# Ethernet_CTRL.net
KiCad netlist of a schematic drawn in Altium Designer
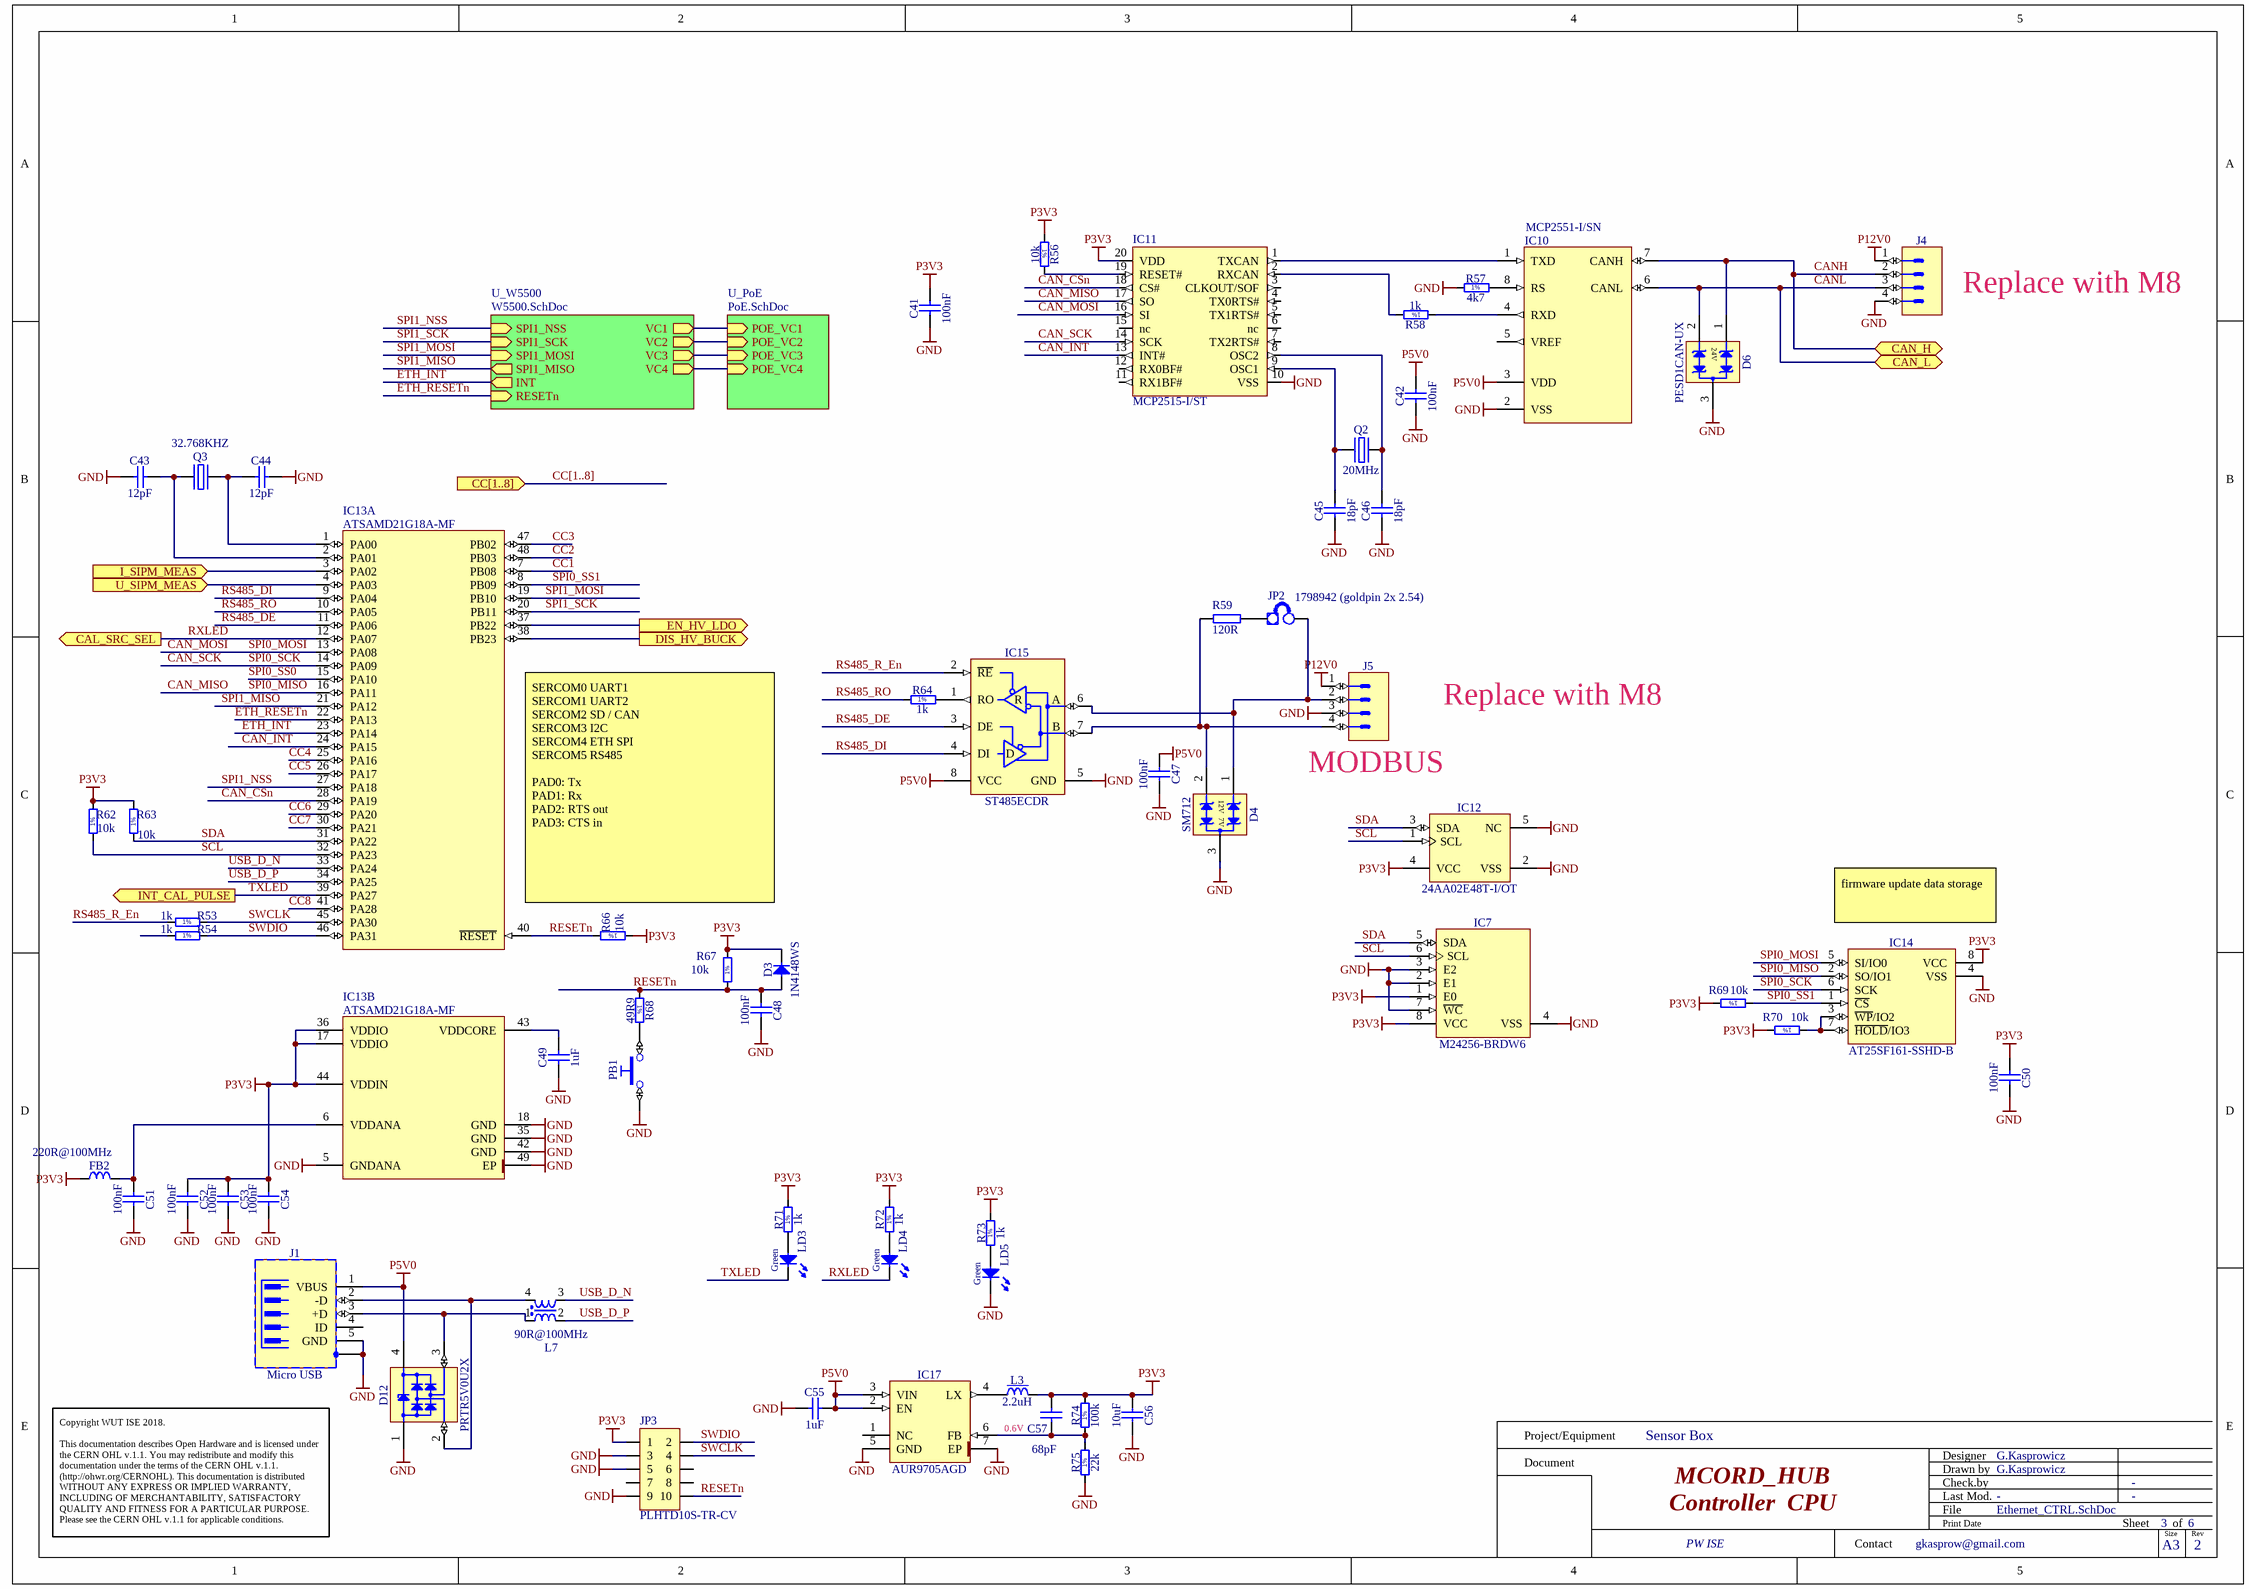
[diagram p0: Ethernet_CTRL.SchDoc]

(export (version "E")
  (design (tool "Eeschema 10.0.6"))
  (components
    (comp (ref "C41")
      (value "100nF")
      (footprint "CAPC1005X55N")
      (description "Non-polarised capacitor")
      (fields
        (field (name "PART NUMBER") "CC0402_100NF_16V_10%_X5R")
        (field (name "VOLTAGE") "16V")
        (field (name "AUTHOR") "CERN DEM JLC")
      )
      (libsource (lib "Capacitors") (part "Capacitor - non polarized"))
    )
    (comp (ref "C42")
      (value "100nF")
      (footprint "CAPC1005X55N")
      (description "Non-polarised capacitor")
      (fields
        (field (name "PART NUMBER") "CC0402_100NF_16V_10%_X5R")
        (field (name "VOLTAGE") "16V")
        (field (name "AUTHOR") "CERN DEM JLC")
      )
      (libsource (lib "Capacitors") (part "Capacitor - non polarized"))
    )
    (comp (ref "C43")
      (value "12pF")
      (footprint "CAPC1005X55N")
      (description "Non-polarised capacitor")
      (fields
        (field (name "PART NUMBER") "CC0402_12PF_50V_5%_C0G")
        (field (name "VOLTAGE") "50V")
        (field (name "AUTHOR") "CERN DEM JLC")
      )
      (libsource (lib "Capacitors") (part "Capacitor - non polarized"))
    )
    (comp (ref "C44")
      (value "12pF")
      (footprint "CAPC1005X55N")
      (description "Non-polarised capacitor")
      (fields
        (field (name "PART NUMBER") "CC0402_12PF_50V_5%_C0G")
        (field (name "VOLTAGE") "50V")
        (field (name "AUTHOR") "CERN DEM JLC")
      )
      (libsource (lib "Capacitors") (part "Capacitor - non polarized"))
    )
    (comp (ref "C45")
      (value "18pF")
      (footprint "CAPC1005X55N")
      (description "Non-polarised capacitor")
      (fields
        (field (name "PART NUMBER") "CC0402_18PF_50V_5%_C0G")
        (field (name "VOLTAGE") "50V")
        (field (name "AUTHOR") "CERN DEM JLC")
      )
      (libsource (lib "Capacitors") (part "Capacitor - non polarized"))
    )
    (comp (ref "C46")
      (value "18pF")
      (footprint "CAPC1005X55N")
      (description "Non-polarised capacitor")
      (fields
        (field (name "PART NUMBER") "CC0402_18PF_50V_5%_C0G")
        (field (name "VOLTAGE") "50V")
        (field (name "AUTHOR") "CERN DEM JLC")
      )
      (libsource (lib "Capacitors") (part "Capacitor - non polarized"))
    )
    (comp (ref "C47")
      (value "100nF")
      (footprint "CAPC1005X55N")
      (description "Non-polarised capacitor")
      (fields
        (field (name "PART NUMBER") "CC0402_100NF_16V_10%_X7R")
        (field (name "VOLTAGE") "16V")
        (field (name "AUTHOR") "CERN DEM JLC")
      )
      (libsource (lib "Capacitors") (part "Capacitor - non polarized"))
    )
    (comp (ref "C48")
      (value "100nF")
      (footprint "CAPC1005X55N")
      (description "Non-polarised capacitor")
      (fields
        (field (name "PART NUMBER") "CC0402_100NF_16V_10%_X7R")
        (field (name "VOLTAGE") "16V")
        (field (name "AUTHOR") "CERN DEM JLC")
      )
      (libsource (lib "Capacitors") (part "Capacitor - non polarized"))
    )
    (comp (ref "C49")
      (value "1uF")
      (footprint "CAPC1608X87N")
      (description "Non-polarised capacitor")
      (fields
        (field (name "PART NUMBER") "CC0603_1UF_16V_10%_X7R")
        (field (name "VOLTAGE") "16V")
        (field (name "AUTHOR") "CERN DEM JLC")
      )
      (libsource (lib "Capacitors") (part "Capacitor - non polarized"))
    )
    (comp (ref "C50")
      (value "100nF")
      (footprint "CAPC1005X55N")
      (description "Non-polarised capacitor")
      (fields
        (field (name "PART NUMBER") "CC0402_100NF_16V_10%_X7R")
        (field (name "VOLTAGE") "16V")
        (field (name "AUTHOR") "CERN DEM JLC")
      )
      (libsource (lib "Capacitors") (part "Capacitor - non polarized"))
    )
    (comp (ref "C51")
      (value "100nF")
      (footprint "CAPC1005X55N")
      (description "Non-polarised capacitor")
      (fields
        (field (name "PART NUMBER") "CC0402_100NF_16V_10%_X7R")
        (field (name "VOLTAGE") "16V")
        (field (name "AUTHOR") "CERN DEM JLC")
      )
      (libsource (lib "Capacitors") (part "Capacitor - non polarized"))
    )
    (comp (ref "C52")
      (value "100nF")
      (footprint "CAPC1005X55N")
      (description "Non-polarised capacitor")
      (fields
        (field (name "PART NUMBER") "CC0402_100NF_16V_10%_X7R")
        (field (name "VOLTAGE") "16V")
        (field (name "AUTHOR") "CERN DEM JLC")
      )
      (libsource (lib "Capacitors") (part "Capacitor - non polarized"))
    )
    (comp (ref "C53")
      (value "100nF")
      (footprint "CAPC1005X55N")
      (description "Non-polarised capacitor")
      (fields
        (field (name "PART NUMBER") "CC0402_100NF_16V_10%_X7R")
        (field (name "VOLTAGE") "16V")
        (field (name "AUTHOR") "CERN DEM JLC")
      )
      (libsource (lib "Capacitors") (part "Capacitor - non polarized"))
    )
    (comp (ref "C54")
      (value "100nF")
      (footprint "CAPC1005X55N")
      (description "Non-polarised capacitor")
      (fields
        (field (name "PART NUMBER") "CC0402_100NF_16V_10%_X7R")
        (field (name "VOLTAGE") "16V")
        (field (name "AUTHOR") "CERN DEM JLC")
      )
      (libsource (lib "Capacitors") (part "Capacitor - non polarized"))
    )
    (comp (ref "C55")
      (value "1uF")
      (footprint "CAPC1005X55N")
      (description "Non-polarised capacitor")
      (fields
        (field (name "PART NUMBER") "CC0402_1UF_16V_10%_X5R")
        (field (name "VOLTAGE") "16V")
        (field (name "AUTHOR") "CERN DEM JLC")
      )
      (libsource (lib "Capacitors") (part "Capacitor - non polarized"))
    )
    (comp (ref "C56")
      (value "10uF")
      (footprint "CAPC2012X135N")
      (description "Non-polarised capacitor")
      (fields
        (field (name "PART NUMBER") "CC0805_10UF_16V_10%_X5R")
        (field (name "VOLTAGE") "16V")
        (field (name "AUTHOR") "CERN DEM JLC")
      )
      (libsource (lib "Capacitors") (part "Capacitor - non polarized"))
    )
    (comp (ref "C57")
      (value "68pF")
      (footprint "CAPC1608X87N")
      (description "Non-polarised capacitor")
      (fields
        (field (name "PART NUMBER") "CC0603_68PF_50V_5%_NP0")
        (field (name "VOLTAGE") "50V")
        (field (name "AUTHOR") "CERN DEM JLC")
      )
      (libsource (lib "Capacitors") (part "Capacitor - non polarized"))
    )
    (comp (ref "D3")
      (value "1N4148WS")
      (footprint "SODFL2512X100N")
      (description "Diode")
      (fields
        (field (name "VOLTAGE") "75V")
        (field (name "POWER") "150mA")
        (field (name "AUTHOR") "CERN DEM JLC")
      )
      (libsource (lib "ICs And Semiconductors") (part "Diode"))
    )
    (comp (ref "D4")
      (value "SM712")
      (footprint "SOT95P237X112-3N")
      (description "Asymmetrical TVS Diode for Extended Common-Mode RS-485")
      (fields
        (field (name "VOLTAGE") "12V/-7V")
        (field (name "POWER") "400W")
        (field (name "AUTHOR") "CERN DEM JLC")
      )
      (libsource (lib "ICs And Semiconductors") (part "SM712"))
    )
    (comp (ref "D6")
      (value "PESD1CAN-UX")
      (footprint "SOT95P237X112-3N")
      (description "TVS Diode for CAN")
      (fields
        (field (name "VOLTAGE") "24V")
        (field (name "POWER") "400W")
        (field (name "AUTHOR") "CERN DEM JLC")
      )
      (libsource (lib "LIBRARY_SCH") (part "D_TVS_PESD1CAN"))
    )
    (comp (ref "D12")
      (value "PRTR5V0U2X")
      (footprint "SOT190P230X110-4N")
      (description "Ultra Low Capacitance Double Rail-to-Rail ESD Protection Diode")
      (fields
        (field (name "VOLTAGE") "5.5V")
        (field (name "MANUFACTURER") "NXP SEMICONDUCTORS")
        (field (name "AUTHOR") "CERN DEM JLC")
      )
      (libsource (lib "ICs And Semiconductors") (part "PRTR5V0U2X"))
    )
    (comp (ref "FB2")
      (value "220R@100MHz")
      (footprint "INDC2012X105N")
      (description "Inductor")
      (fields
        (field (name "PART NUMBER") "IND0805_MURATA_BLM21PG221SN1D")
        (field (name "POWER") "2A")
        (field (name "AUTHOR") "CERN DEM JLC")
      )
      (libsource (lib "Inductors & Transformers") (part "Inductor"))
    )
    (comp (ref "IC7")
      (value "M24256-BRDW6")
      (footprint "SOP65P640X120-8N")
      (description "256-Kbit Serial I²C Bus EEPROM")
      (fields
        (field (name "PART NUMBER") "M24256-BRDW6P")
        (field (name "MANUFACTURER") "ST MICROELECTRONICS")
        (field (name "AUTHOR") "CERN DEM MR")
      )
      (libsource (lib "LIBRARY_SCH") (part "MEM_M24256-BRDW6P"))
    )
    (comp (ref "IC10")
      (value "MCP2551-I/SN")
      (footprint "SOIC127P600X175-8N")
      (description "High-Speed CAN Transceiver, 8-Pin SOIC, Industrial Temperature")
      (fields (field (name "MANUFACTURER") "MICROCHIP TECHNOLOGY") (field (name "AUTHOR") "GK"))
      (libsource (lib "LIBRARY_SCH") (part "IFC_MCP2551"))
    )
    (comp (ref "IC11")
      (value "MCP2515-I/ST")
      (footprint "SOP65P640X110-20N")
      (description "CAN Controller With SPI nterface")
      (fields
        (field (name "MANUFACTURER") "Microchip")
        (field (name "MANUFACTURER PART NUMBER") "MCP2515T-I/ST")
      )
      (libsource (lib "LIBRARY_SCH") (part "IFC_MCP2515_TSSOP"))
    )
    (comp (ref "IC12")
      (value "24AA02E48T-I/OT")
      (footprint "SOT95P280X145-5N")
      (description "1.7V-5.5V, 2K I2C Serial EEPROM With EUI-48 Node Identity")
      (fields (field (name "MANUFACTURER") "MICROCHIP TECHNOLOGY") (field (name "AUTHOR") "CERN DEM MR"))
      (libsource (lib "ICs And Semiconductors") (part "24AA02E48T-I/OT"))
    )
    (comp (ref "IC13")
      (value "ATSAMD21G18A-MF")
      (footprint "QFN50P700X700X100-49N-S525")
      (fields (field (name "MANUFACTURER") "MICROCHIP") (field (name "AUTHOR") "CERN DEM BC"))
      (libsource (lib "ICs And Semiconductors") (part "ATSAMD21G18A-MF"))
    )
    (comp (ref "IC14")
      (value "AT25SF161-SSHD-B")
      (footprint "SOIC127P790X216-8N")
      (description "16Mb, 3V, Multiple I/O Serial NOR Flash Memory")
      (fields (field (name "AUTHOR") "GK"))
      (libsource (lib "LIBRARY_SCH") (part "MEM_AT25SF161"))
    )
    (comp (ref "IC15")
      (value "ST485ECDR")
      (footprint "SOIC127P600X175-8N")
      (description "±15kV ESD-Protected, Low Power  RS-485/RS-422 Transceiver")
      (fields (field (name "MANUFACTURER") "ST MICROELECTRONICS") (field (name "AUTHOR") "CERN DEM MR"))
      (libsource (lib "ICs And Semiconductors") (part "ST485EC"))
    )
    (comp (ref "IC17")
      (value "AUR9705AGD")
      (footprint "SON65P200X200X80-7N-R65X145")
      (description "0V to 6V Input, 1A, 1.5MHz, Step-Down DC-DC Converter")
      (fields (field (name "MANUFACTURER") "DIODES INCORPORATED") (field (name "AUTHOR") "CERN DEM MR"))
      (libsource (lib "ICs And Semiconductors") (part "AUR9705AGD"))
    )
    (comp (ref "J1")
      (value "Micro USB")
      (footprint "FCI_10118194-0001LF")
      (description "5 Pin + 1 Shield USB Receptacle")
      (fields
        (field (name "PART NUMBER") "FCI_10118194-0001LF")
        (field (name "MANUFACTURER") "FCI")
        (field (name "AUTHOR") "CERN DEM JLC")
      )
      (libsource (lib "Connectors") (part "Connector USB 5 Pin + 1Shield"))
    )
    (comp (ref "J4")
      (value "~")
      (footprint "FCI_20020110-D041A01LF")
      (description "Connector 4 Male")
      (fields
        (field (name "PART NUMBER") "FCI_20020110-D041A01LF")
        (field (name "MANUFACTURER") "FCI")
        (field (name "AUTHOR") "CERN DEM JLC")
      )
      (libsource (lib "Connectors") (part "Connector 4 Male"))
    )
    (comp (ref "J5")
      (value "~")
      (footprint "FCI_20020110-D041A01LF")
      (description "Connector 4 Male")
      (fields
        (field (name "PART NUMBER") "FCI_20020110-D041A01LF")
        (field (name "MANUFACTURER") "FCI")
        (field (name "AUTHOR") "CERN DEM JLC")
      )
      (libsource (lib "Connectors") (part "Connector 4 Male"))
    )
    (comp (ref "JP2")
      (value "1798942 (goldpin 2x 2.54)")
      (footprint "jump")
      (description "Jumper")
      (libsource (lib "LIBRARY_SCH") (part "JUMPER"))
    )
    (comp (ref "JP3")
      (value "PLHTD10S-TR-CV")
      (footprint "PLHTD10S-TR-CV")
      (description "1.27 mm dual row goldpin (Maritex)")
      (libsource (lib "LIBRARY_SCH") (part "CON_2x5 1.27 SMT Male"))
    )
    (comp (ref "L3")
      (value "2.2uH")
      (footprint "IND_MURATA_LQH44PN_P0")
      (description "Inductor With Core")
      (fields
        (field (name "PART NUMBER") "IND_2.2UH_20%_MURATA_LQH44PN2R2MP0L")
        (field (name "POWER") "1.8A")
        (field (name "AUTHOR") "CERN DEM JLC")
      )
      (libsource (lib "Inductors & Transformers") (part "Inductor With Magnetic core"))
    )
    (comp (ref "L7")
      (value "90R@100MHz")
      (footprint "IND_MURATA_DLW21S")
      (description "Inductor Common Mode")
      (fields
        (field (name "PART NUMBER") "IND_MURATA_DLW21SN900SQ2L")
        (field (name "POWER") "330mA")
        (field (name "AUTHOR") "CERN DEM JLC")
      )
      (libsource (lib "Inductors & Transformers") (part "Inductor Common Mode 1Dot-2 4Dot-3"))
    )
    (comp (ref "LD3")
      (value "Green")
      (footprint "LED_AVAGO_HSME-C120")
      (description "LED Green 1C 2A")
      (fields
        (field (name "PART NUMBER") "LED_AVAGO_HSME-C120")
        (field (name "MANUFACTURER") "AVAGO TECHNOLOGIES")
        (field (name "AUTHOR") "CERN DEM JMW")
      )
      (libsource (lib "ICs And Semiconductors") (part "LED Green 1C 2A"))
    )
    (comp (ref "LD4")
      (value "Green")
      (footprint "LED_AVAGO_HSME-C120")
      (description "LED Green 1C 2A")
      (fields
        (field (name "PART NUMBER") "LED_AVAGO_HSME-C120")
        (field (name "MANUFACTURER") "AVAGO TECHNOLOGIES")
        (field (name "AUTHOR") "CERN DEM JMW")
      )
      (libsource (lib "ICs And Semiconductors") (part "LED Green 1C 2A"))
    )
    (comp (ref "LD5")
      (value "Green")
      (footprint "LED_AVAGO_HSME-C120")
      (description "LED Green 1C 2A")
      (fields
        (field (name "PART NUMBER") "LED_AVAGO_HSME-C120")
        (field (name "MANUFACTURER") "AVAGO TECHNOLOGIES")
        (field (name "AUTHOR") "CERN DEM JMW")
      )
      (libsource (lib "ICs And Semiconductors") (part "LED Green 1C 2A"))
    )
    (comp (ref "PB1")
      (value "Push Button")
      (footprint "PB_TYCO_FSMSM")
      (description "Push-Button Switch SPDT")
      (fields
        (field (name "PART NUMBER") "PB_TYCO_FSMSM")
        (field (name "MANUFACTURER") "TYCO ELECTRONICS")
        (field (name "AUTHOR") "CERN DEM JLC")
      )
      (libsource (lib "Eletro-mechanical") (part "PB SPST 1NO-2NO"))
    )
    (comp (ref "Q2")
      (value "20MHz")
      (footprint "XTAL1160X490X430")
      (description "Quartz Crystal 20MHz, 30ppm, 20pF")
      (fields
        (field (name "PART NUMBER") "SR PASSIVES 20M-49SMD-SR")
        (field (name "MANUFACTURER") "SR PASSIVES")
        (field (name "AUTHOR") "GK")
      )
      (libsource (lib "LIBRARY_SCH") (part "X_CRYSTAL_20M_HC49"))
    )
    (comp (ref "Q3")
      (value "32.768KHZ")
      (footprint "XTAL_ABRACON_ABS09")
      (description "Quartz Crystal")
      (fields
        (field (name "PART NUMBER") "XTAL_32.768KHZ_ABRACON_ABS09-32.768KHZ-T")
        (field (name "MANUFACTURER") "ABRACON")
        (field (name "AUTHOR") "CERN DEM JLC")
      )
      (libsource (lib "ICs And Semiconductors") (part "Quartz Crystal"))
    )
    (comp (ref "R53")
      (value "1k")
      (footprint "RESC1005X40N")
      (description "Resistor - 1%")
      (fields
        (field (name "PART NUMBER") "R0402_1K_1%_0.0625W_100PPM")
        (field (name "POWER") "0.0625W")
        (field (name "AUTHOR") "CERN DEM JLC")
      )
      (libsource (lib "Resistors") (part "Resistor - 1%"))
    )
    (comp (ref "R54")
      (value "1k")
      (footprint "RESC1005X40N")
      (description "Resistor - 1%")
      (fields
        (field (name "PART NUMBER") "R0402_1K_1%_0.0625W_100PPM")
        (field (name "POWER") "0.0625W")
        (field (name "AUTHOR") "CERN DEM JLC")
      )
      (libsource (lib "Resistors") (part "Resistor - 1%"))
    )
    (comp (ref "R56")
      (value "10k")
      (footprint "RESC1005X40N")
      (description "Resistor - 1%")
      (fields
        (field (name "PART NUMBER") "R0402_10K_1%_0.0625W_100PPM")
        (field (name "POWER") "0.0625W")
        (field (name "AUTHOR") "CERN DEM JLC")
      )
      (libsource (lib "Resistors") (part "Resistor - 1%"))
    )
    (comp (ref "R57")
      (value "4k7")
      (footprint "RESC1005X40N")
      (description "Resistor - 1%")
      (fields
        (field (name "PART NUMBER") "R0402_4K7_1%_0.0625W_100PPM")
        (field (name "POWER") "0.0625W")
        (field (name "AUTHOR") "CERN DEM JLC")
      )
      (libsource (lib "Resistors") (part "Resistor - 1%"))
    )
    (comp (ref "R58")
      (value "1k")
      (footprint "RESC1005X40N")
      (description "Resistor - 1%")
      (fields
        (field (name "PART NUMBER") "R0402_1K_1%_0.0625W_100PPM")
        (field (name "POWER") "0.0625W")
        (field (name "AUTHOR") "CERN DEM JLC")
      )
      (libsource (lib "Resistors") (part "Resistor - 1%"))
    )
    (comp (ref "R59")
      (value "120R")
      (footprint "1206R")
      (description "SMD Resistor")
      (libsource (lib "LIBRARY_SCH") (part "RES_1206"))
    )
    (comp (ref "R62")
      (value "10k")
      (footprint "RESC1005X40N")
      (description "Resistor - 1%")
      (fields
        (field (name "PART NUMBER") "R0402_10K_1%_0.0625W_100PPM")
        (field (name "POWER") "0.0625W")
        (field (name "AUTHOR") "CERN DEM JLC")
      )
      (libsource (lib "Resistors") (part "Resistor - 1%"))
    )
    (comp (ref "R63")
      (value "10k")
      (footprint "RESC1005X40N")
      (description "Resistor - 1%")
      (fields
        (field (name "PART NUMBER") "R0402_10K_1%_0.0625W_100PPM")
        (field (name "POWER") "0.0625W")
        (field (name "AUTHOR") "CERN DEM JLC")
      )
      (libsource (lib "Resistors") (part "Resistor - 1%"))
    )
    (comp (ref "R64")
      (value "1k")
      (footprint "RESC1005X40N")
      (description "Resistor - 1%")
      (fields
        (field (name "PART NUMBER") "R0402_1K_1%_0.0625W_100PPM")
        (field (name "POWER") "0.0625W")
        (field (name "AUTHOR") "CERN DEM JLC")
      )
      (libsource (lib "Resistors") (part "Resistor - 1%"))
    )
    (comp (ref "R66")
      (value "10k")
      (footprint "RESC1005X40N")
      (description "Resistor - 1%")
      (fields
        (field (name "PART NUMBER") "R0402_10K_1%_0.0625W_100PPM")
        (field (name "POWER") "0.0625W")
        (field (name "AUTHOR") "CERN DEM JLC")
      )
      (libsource (lib "Resistors") (part "Resistor - 1%"))
    )
    (comp (ref "R67")
      (value "10k")
      (footprint "RESC1005X40N")
      (description "Resistor - 1%")
      (fields
        (field (name "PART NUMBER") "R0402_10K_1%_0.0625W_100PPM")
        (field (name "POWER") "0.0625W")
        (field (name "AUTHOR") "CERN DEM JLC")
      )
      (libsource (lib "Resistors") (part "Resistor - 1%"))
    )
    (comp (ref "R68")
      (value "49R9")
      (footprint "RESC1005X40N")
      (description "Resistor - 1%")
      (fields
        (field (name "PART NUMBER") "R0402_49R9_1%_0.0625W_100PPM")
        (field (name "POWER") "0.0625W")
        (field (name "AUTHOR") "CERN DEM JLC")
      )
      (libsource (lib "Resistors") (part "Resistor - 1%"))
    )
    (comp (ref "R69")
      (value "10k")
      (footprint "RESC1005X40N")
      (description "Resistor - 1%")
      (fields
        (field (name "PART NUMBER") "R0402_10K_1%_0.0625W_100PPM")
        (field (name "POWER") "0.0625W")
        (field (name "AUTHOR") "CERN DEM JLC")
      )
      (libsource (lib "Resistors") (part "Resistor - 1%"))
    )
    (comp (ref "R70")
      (value "10k")
      (footprint "RESC1005X40N")
      (description "Resistor - 1%")
      (fields
        (field (name "PART NUMBER") "R0402_10K_1%_0.0625W_100PPM")
        (field (name "POWER") "0.0625W")
        (field (name "AUTHOR") "CERN DEM JLC")
      )
      (libsource (lib "Resistors") (part "Resistor - 1%"))
    )
    (comp (ref "R71")
      (value "1k")
      (footprint "RESC1005X40N")
      (description "Resistor - 1%")
      (fields
        (field (name "PART NUMBER") "R0402_1K_1%_0.0625W_100PPM")
        (field (name "POWER") "0.0625W")
        (field (name "AUTHOR") "CERN DEM JLC")
      )
      (libsource (lib "Resistors") (part "Resistor - 1%"))
    )
    (comp (ref "R72")
      (value "1k")
      (footprint "RESC1005X40N")
      (description "Resistor - 1%")
      (fields
        (field (name "PART NUMBER") "R0402_1K_1%_0.0625W_100PPM")
        (field (name "POWER") "0.0625W")
        (field (name "AUTHOR") "CERN DEM JLC")
      )
      (libsource (lib "Resistors") (part "Resistor - 1%"))
    )
    (comp (ref "R73")
      (value "1k")
      (footprint "RESC1005X40N")
      (description "Resistor - 1%")
      (fields
        (field (name "PART NUMBER") "R0402_1K_1%_0.0625W_100PPM")
        (field (name "POWER") "0.0625W")
        (field (name "AUTHOR") "CERN DEM JLC")
      )
      (libsource (lib "Resistors") (part "Resistor - 1%"))
    )
    (comp (ref "R74")
      (value "100k")
      (footprint "RESC1005X40N")
      (description "Resistor - 1%")
      (fields
        (field (name "PART NUMBER") "R0402_100K_1%_0.0625W_100PPM")
        (field (name "POWER") "0.0625W")
        (field (name "AUTHOR") "CERN DEM JLC")
      )
      (libsource (lib "Resistors") (part "Resistor - 1%"))
    )
    (comp (ref "R75")
      (value "22k")
      (footprint "RESC1005X40N")
      (description "Resistor - 1%")
      (fields
        (field (name "PART NUMBER") "R0402_22K_1%_0.0625W_100PPM")
        (field (name "POWER") "0.0625W")
        (field (name "AUTHOR") "CERN DEM JLC")
      )
      (libsource (lib "Resistors") (part "Resistor - 1%"))
    )
  )
  (nets
    (net (code "1") (name "/CANH") (class "Default")
      (node (ref "D6") (pin "1") (pinfunction "I/O1_1") (pintype "passive"))
      (node (ref "IC10") (pin "7") (pinfunction "CANH_7") (pintype "bidirectional"))
      (node (ref "J4") (pin "2") (pinfunction "2_2") (pintype "bidirectional"))
    )
    (net (code "2") (name "/CANL") (class "Default")
      (node (ref "D6") (pin "2") (pinfunction "I/O2_2") (pintype "passive"))
      (node (ref "IC10") (pin "6") (pinfunction "CANL_6") (pintype "bidirectional"))
      (node (ref "J4") (pin "3") (pinfunction "3_3") (pintype "bidirectional"))
    )
    (net (code "3") (name "/CAN_CSn") (class "Default")
      (node (ref "IC11") (pin "18") (pinfunction "CS#_18") (pintype "output"))
      (node (ref "IC13") (pin "28") (pinfunction "PA19_28") (pintype "bidirectional"))
    )
    (net (code "4") (name "/CAN_INT") (class "Default")
      (node (ref "IC11") (pin "13") (pinfunction "INT#_13") (pintype "output"))
      (node (ref "IC13") (pin "24") (pinfunction "PA15_24") (pintype "bidirectional"))
    )
    (net (code "5") (name "/CAN_MISO") (class "Default")
      (node (ref "IC11") (pin "17") (pinfunction "SO_17") (pintype "output"))
      (node (ref "IC13") (pin "16") (pinfunction "PA11_16") (pintype "bidirectional"))
      (node (ref "IC14") (pin "2") (pinfunction "SO/IO1_2") (pintype "bidirectional"))
    )
    (net (code "6") (name "/CAN_MOSI") (class "Default")
      (node (ref "IC11") (pin "16") (pinfunction "SI_16") (pintype "input"))
      (node (ref "IC13") (pin "13") (pinfunction "PA08_13") (pintype "bidirectional"))
      (node (ref "IC14") (pin "5") (pinfunction "SI/IO0_5") (pintype "bidirectional"))
    )
    (net (code "7") (name "/CAN_SCK") (class "Default")
      (node (ref "IC11") (pin "14") (pinfunction "SCK_14") (pintype "input"))
      (node (ref "IC13") (pin "14") (pinfunction "PA09_14") (pintype "bidirectional"))
      (node (ref "IC14") (pin "6") (pinfunction "SCK_6") (pintype "input"))
    )
    (net (code "8") (name "/CC1") (class "Default")
      (node (ref "IC13") (pin "7") (pinfunction "PB08_7") (pintype "bidirectional"))
    )
    (net (code "9") (name "/CC2") (class "Default")
      (node (ref "IC13") (pin "48") (pinfunction "PB03_48") (pintype "bidirectional"))
    )
    (net (code "10") (name "/CC3") (class "Default")
      (node (ref "IC13") (pin "47") (pinfunction "PB02_47") (pintype "bidirectional"))
    )
    (net (code "11") (name "/CC4") (class "Default")
      (node (ref "IC13") (pin "25") (pinfunction "PA16_25") (pintype "bidirectional"))
    )
    (net (code "12") (name "/CC5") (class "Default")
      (node (ref "IC13") (pin "26") (pinfunction "PA17_26") (pintype "bidirectional"))
    )
    (net (code "13") (name "/CC6") (class "Default")
      (node (ref "IC13") (pin "29") (pinfunction "PA20_29") (pintype "bidirectional"))
    )
    (net (code "14") (name "/CC7") (class "Default")
      (node (ref "IC13") (pin "30") (pinfunction "PA21_30") (pintype "bidirectional"))
    )
    (net (code "15") (name "/CC8") (class "Default")
      (node (ref "IC13") (pin "41") (pinfunction "PA28_41") (pintype "bidirectional"))
    )
    (net (code "17") (name "/DIS_HV_BUCK") (class "Default")
      (node (ref "IC13") (pin "38") (pinfunction "PB23_38") (pintype "bidirectional"))
    )
    (net (code "18") (name "/EN_HV_LDO") (class "Default")
      (node (ref "IC13") (pin "37") (pinfunction "PB22_37") (pintype "bidirectional"))
    )
    (net (code "19") (name "/ETH_INT") (class "Default")
      (node (ref "IC13") (pin "23") (pinfunction "PA14_23") (pintype "bidirectional"))
    )
    (net (code "20") (name "/ETH_RESETn") (class "Default")
      (node (ref "IC13") (pin "22") (pinfunction "PA13_22") (pintype "bidirectional"))
    )
    (net (code "21") (name "/I_SIPM_MEAS") (class "Default")
      (node (ref "IC13") (pin "3") (pinfunction "PA02_3") (pintype "bidirectional"))
    )
    (net (code "22") (name "/RESETn") (class "Default")
      (node (ref "C48") (pin "1") (pinfunction "1_1") (pintype "passive"))
      (node (ref "D3") (pin "2") (pinfunction "A_2") (pintype "passive"))
      (node (ref "IC13") (pin "40") (pinfunction "~{RESET}_40") (pintype "input"))
      (node (ref "JP3") (pin "10") (pinfunction "10_10") (pintype "passive"))
      (node (ref "R66") (pin "2") (pinfunction "2_2") (pintype "passive"))
      (node (ref "R67") (pin "1") (pinfunction "1_1") (pintype "passive"))
      (node (ref "R68") (pin "1") (pinfunction "1_1") (pintype "passive"))
    )
    (net (code "23") (name "/RS485_DE") (class "Default")
      (node (ref "IC13") (pin "11") (pinfunction "PA06_11") (pintype "bidirectional"))
      (node (ref "IC15") (pin "3") (pinfunction "DE_3") (pintype "input"))
    )
    (net (code "24") (name "/RS485_DI") (class "Default")
      (node (ref "IC13") (pin "9") (pinfunction "PA04_9") (pintype "bidirectional"))
      (node (ref "IC15") (pin "4") (pinfunction "DI_4") (pintype "input"))
    )
    (net (code "25") (name "/RS485_RO") (class "Default")
      (node (ref "IC13") (pin "10") (pinfunction "PA05_10") (pintype "bidirectional"))
      (node (ref "R64") (pin "1") (pinfunction "1_1") (pintype "passive"))
    )
    (net (code "26") (name "/RS485_R_En") (class "Default")
      (node (ref "IC15") (pin "2") (pinfunction "~{RE}_2") (pintype "input"))
      (node (ref "R53") (pin "1") (pinfunction "1_1") (pintype "passive"))
    )
    (net (code "27") (name "/RXLED") (class "Default")
      (node (ref "IC13") (pin "12") (pinfunction "PA07_12") (pintype "bidirectional"))
      (node (ref "LD4") (pin "1") (pinfunction "C_1") (pintype "passive"))
    )
    (net (code "28") (name "/SCL") (class "Default")
      (node (ref "IC12") (pin "1") (pinfunction "SCL_1") (pintype "input"))
      (node (ref "IC13") (pin "32") (pinfunction "PA23_32") (pintype "bidirectional"))
      (node (ref "IC7") (pin "6") (pinfunction "SCL_6") (pintype "input"))
      (node (ref "R62") (pin "1") (pinfunction "1_1") (pintype "passive"))
    )
    (net (code "29") (name "/SDA") (class "Default")
      (node (ref "IC12") (pin "3") (pinfunction "SDA_3") (pintype "bidirectional"))
      (node (ref "IC13") (pin "31") (pinfunction "PA22_31") (pintype "bidirectional"))
      (node (ref "IC7") (pin "5") (pinfunction "SDA_5") (pintype "bidirectional"))
      (node (ref "R63") (pin "1") (pinfunction "1_1") (pintype "passive"))
    )
    (net (code "30") (name "/SPI0_SS0") (class "Default")
      (node (ref "IC13") (pin "15") (pinfunction "PA10_15") (pintype "bidirectional"))
    )
    (net (code "31") (name "/SPI0_SS1") (class "Default")
      (node (ref "IC13") (pin "8") (pinfunction "PB09_8") (pintype "bidirectional"))
      (node (ref "IC14") (pin "1") (pinfunction "~{CS}_1") (pintype "input"))
      (node (ref "R69") (pin "1") (pinfunction "1_1") (pintype "passive"))
    )
    (net (code "32") (name "/SPI1_MISO") (class "Default")
      (node (ref "IC13") (pin "21") (pinfunction "PA12_21") (pintype "bidirectional"))
    )
    (net (code "33") (name "/SPI1_MOSI") (class "Default")
      (node (ref "IC13") (pin "19") (pinfunction "PB10_19") (pintype "bidirectional"))
    )
    (net (code "34") (name "/SPI1_NSS") (class "Default")
      (node (ref "IC13") (pin "27") (pinfunction "PA18_27") (pintype "bidirectional"))
    )
    (net (code "35") (name "/SPI1_SCK") (class "Default")
      (node (ref "IC13") (pin "20") (pinfunction "PB11_20") (pintype "bidirectional"))
    )
    (net (code "36") (name "/SWCLK") (class "Default")
      (node (ref "IC13") (pin "45") (pinfunction "PA30_45") (pintype "bidirectional"))
      (node (ref "JP3") (pin "4") (pinfunction "4_4") (pintype "passive"))
      (node (ref "R53") (pin "2") (pinfunction "2_2") (pintype "passive"))
    )
    (net (code "37") (name "/SWDIO") (class "Default")
      (node (ref "IC13") (pin "46") (pinfunction "PA31_46") (pintype "bidirectional"))
      (node (ref "JP3") (pin "2") (pinfunction "2_2") (pintype "passive"))
      (node (ref "R54") (pin "2") (pinfunction "2_2") (pintype "passive"))
    )
    (net (code "38") (name "/TXLED") (class "Default")
      (node (ref "IC13") (pin "39") (pinfunction "PA27_39") (pintype "bidirectional"))
      (node (ref "LD3") (pin "1") (pinfunction "C_1") (pintype "passive"))
    )
    (net (code "39") (name "/USB_D_N") (class "Default")
      (node (ref "IC13") (pin "33") (pinfunction "PA24_33") (pintype "bidirectional"))
      (node (ref "L7") (pin "3") (pinfunction "3_3") (pintype "passive"))
    )
    (net (code "40") (name "/USB_D_P") (class "Default")
      (node (ref "IC13") (pin "34") (pinfunction "PA25_34") (pintype "bidirectional"))
      (node (ref "L7") (pin "2") (pinfunction "2_2") (pintype "passive"))
    )
    (net (code "41") (name "/U_SIPM_MEAS") (class "Default")
      (node (ref "IC13") (pin "4") (pinfunction "PA03_4") (pintype "bidirectional"))
    )
    (net (code "46") (name "GND") (class "Default")
      (node (ref "C41") (pin "1") (pinfunction "1_1") (pintype "passive"))
      (node (ref "C42") (pin "1") (pinfunction "1_1") (pintype "passive"))
      (node (ref "C43") (pin "1") (pinfunction "1_1") (pintype "passive"))
      (node (ref "C44") (pin "2") (pinfunction "2_2") (pintype "passive"))
      (node (ref "C45") (pin "1") (pinfunction "1_1") (pintype "passive"))
      (node (ref "C46") (pin "1") (pinfunction "1_1") (pintype "passive"))
      (node (ref "C47") (pin "2") (pinfunction "2_2") (pintype "passive"))
      (node (ref "C48") (pin "2") (pinfunction "2_2") (pintype "passive"))
      (node (ref "C49") (pin "1") (pinfunction "1_1") (pintype "passive"))
      (node (ref "C50") (pin "2") (pinfunction "2_2") (pintype "passive"))
      (node (ref "C51") (pin "2") (pinfunction "2_2") (pintype "passive"))
      (node (ref "C52") (pin "2") (pinfunction "2_2") (pintype "passive"))
      (node (ref "C53") (pin "2") (pinfunction "2_2") (pintype "passive"))
      (node (ref "C54") (pin "2") (pinfunction "2_2") (pintype "passive"))
      (node (ref "C55") (pin "1") (pinfunction "1_1") (pintype "passive"))
      (node (ref "C56") (pin "2") (pinfunction "2_2") (pintype "passive"))
      (node (ref "D12") (pin "1") (pinfunction "GND_1") (pintype "power_in"))
      (node (ref "D4") (pin "3") (pinfunction "GND_3") (pintype "passive"))
      (node (ref "D6") (pin "3") (pinfunction "GND_3") (pintype "passive"))
      (node (ref "IC10") (pin "2") (pinfunction "VSS_2") (pintype "power_in"))
      (node (ref "IC11") (pin "10") (pinfunction "VSS_10") (pintype "power_in"))
      (node (ref "IC12") (pin "2") (pinfunction "VSS_2") (pintype "power_in"))
      (node (ref "IC12") (pin "5") (pinfunction "NC_5") (pintype "passive"))
      (node (ref "IC13") (pin "18") (pinfunction "GND_18") (pintype "power_in"))
      (node (ref "IC13") (pin "35") (pinfunction "GND_35") (pintype "power_in"))
      (node (ref "IC13") (pin "42") (pinfunction "GND_42") (pintype "power_in"))
      (node (ref "IC13") (pin "49") (pinfunction "EP_49") (pintype "passive"))
      (node (ref "IC13") (pin "5") (pinfunction "GNDANA_5") (pintype "power_in"))
      (node (ref "IC14") (pin "4") (pinfunction "VSS_4") (pintype "power_in"))
      (node (ref "IC15") (pin "5") (pinfunction "GND_5") (pintype "power_in"))
      (node (ref "IC17") (pin "5") (pinfunction "GND_5") (pintype "power_in"))
      (node (ref "IC17") (pin "7") (pinfunction "EP_7") (pintype "passive"))
      (node (ref "IC7") (pin "2") (pinfunction "E1_2") (pintype "input"))
      (node (ref "IC7") (pin "3") (pinfunction "E2_3") (pintype "input"))
      (node (ref "IC7") (pin "4") (pinfunction "VSS_4") (pintype "power_in"))
      (node (ref "IC7") (pin "7") (pinfunction "~{WC}_7") (pintype "input"))
      (node (ref "J1") (pin "5") (pinfunction "GND_5") (pintype "power_in"))
      (node (ref "J1") (pin "6") (pinfunction "SH_6") (pintype "power_in"))
      (node (ref "J4") (pin "4") (pinfunction "4_4") (pintype "bidirectional"))
      (node (ref "J5") (pin "3") (pinfunction "3_3") (pintype "bidirectional"))
      (node (ref "JP3") (pin "3") (pinfunction "3_3") (pintype "passive"))
      (node (ref "JP3") (pin "5") (pinfunction "5_5") (pintype "passive"))
      (node (ref "JP3") (pin "9") (pinfunction "9_9") (pintype "passive"))
      (node (ref "LD5") (pin "1") (pinfunction "C_1") (pintype "passive"))
      (node (ref "PB1") (pin "1") (pinfunction "1_1") (pintype "bidirectional"))
      (node (ref "R57") (pin "1") (pinfunction "1_1") (pintype "passive"))
      (node (ref "R75") (pin "1") (pinfunction "1_1") (pintype "passive"))
    )
    (net (code "47") (name "Net-(D4-I{slash}O1)") (class "Default")
      (node (ref "D4") (pin "1") (pinfunction "I/O1_1") (pintype "passive"))
      (node (ref "IC15") (pin "6") (pinfunction "A_6") (pintype "bidirectional"))
      (node (ref "J5") (pin "2") (pinfunction "2_2") (pintype "bidirectional"))
      (node (ref "JP2") (pin "2") (pinfunction "E2_2") (pintype "passive"))
    )
    (net (code "48") (name "Net-(D4-I{slash}O2)") (class "Default")
      (node (ref "D4") (pin "2") (pinfunction "I/O2_2") (pintype "passive"))
      (node (ref "IC15") (pin "7") (pinfunction "B_7") (pintype "bidirectional"))
      (node (ref "J5") (pin "4") (pinfunction "4_4") (pintype "bidirectional"))
      (node (ref "R59") (pin "1") (pinfunction "1_1") (pintype "passive"))
    )
    (net (code "49") (name "Net-(D12-I{slash}O1)") (class "Default")
      (node (ref "D12") (pin "2") (pinfunction "I/O1_2") (pintype "bidirectional"))
      (node (ref "J1") (pin "2") (pinfunction "-D_2") (pintype "bidirectional"))
      (node (ref "L7") (pin "4") (pinfunction "4_4") (pintype "passive"))
    )
    (net (code "50") (name "Net-(D12-I{slash}O2)") (class "Default")
      (node (ref "D12") (pin "3") (pinfunction "I/O2_3") (pintype "bidirectional"))
      (node (ref "J1") (pin "3") (pinfunction "+D_3") (pintype "bidirectional"))
      (node (ref "L7") (pin "1") (pinfunction "1_1") (pintype "passive"))
    )
    (net (code "51") (name "Net-(IC10-RS)") (class "Default")
      (node (ref "IC10") (pin "8") (pinfunction "RS_8") (pintype "input"))
      (node (ref "R57") (pin "2") (pinfunction "2_2") (pintype "passive"))
    )
    (net (code "52") (name "Net-(IC10-RXD)") (class "Default")
      (node (ref "IC10") (pin "4") (pinfunction "RXD_4") (pintype "output"))
      (node (ref "R58") (pin "1") (pinfunction "1_1") (pintype "passive"))
    )
    (net (code "53") (name "Net-(IC10-TXD)") (class "Default")
      (node (ref "IC10") (pin "1") (pinfunction "TXD_1") (pintype "input"))
      (node (ref "IC11") (pin "1") (pinfunction "TXCAN_1") (pintype "output"))
    )
    (net (code "54") (name "Net-(IC11-OSC1)") (class "Default")
      (node (ref "C45") (pin "2") (pinfunction "2_2") (pintype "passive"))
      (node (ref "IC11") (pin "9") (pinfunction "OSC1_9") (pintype "input"))
      (node (ref "Q2") (pin "1") (pinfunction "OSC1_1") (pintype "passive"))
    )
    (net (code "55") (name "Net-(IC11-OSC2)") (class "Default")
      (node (ref "C46") (pin "2") (pinfunction "2_2") (pintype "passive"))
      (node (ref "IC11") (pin "8") (pinfunction "OSC2_8") (pintype "output"))
      (node (ref "Q2") (pin "2") (pinfunction "OSC2_2") (pintype "passive"))
    )
    (net (code "56") (name "Net-(IC11-RESET#)") (class "Default")
      (node (ref "IC11") (pin "19") (pinfunction "RESET#_19") (pintype "input"))
      (node (ref "R56") (pin "2") (pinfunction "2_2") (pintype "passive"))
    )
    (net (code "57") (name "Net-(IC11-RXCAN)") (class "Default")
      (node (ref "IC11") (pin "2") (pinfunction "RXCAN_2") (pintype "input"))
      (node (ref "R58") (pin "2") (pinfunction "2_2") (pintype "passive"))
    )
    (net (code "58") (name "Net-(IC13A-PA00)") (class "Default")
      (node (ref "C44") (pin "1") (pinfunction "1_1") (pintype "passive"))
      (node (ref "IC13") (pin "1") (pinfunction "PA00_1") (pintype "bidirectional"))
      (node (ref "Q3") (pin "2") (pinfunction "OSC2_2") (pintype "passive"))
    )
    (net (code "59") (name "Net-(IC13A-PA01)") (class "Default")
      (node (ref "C43") (pin "2") (pinfunction "2_2") (pintype "passive"))
      (node (ref "IC13") (pin "2") (pinfunction "PA01_2") (pintype "bidirectional"))
      (node (ref "Q3") (pin "1") (pinfunction "OSC1_1") (pintype "passive"))
    )
    (net (code "60") (name "Net-(IC13B-VDDANA)") (class "Default")
      (node (ref "C51") (pin "1") (pinfunction "1_1") (pintype "passive"))
      (node (ref "FB2") (pin "2") (pinfunction "2_2") (pintype "passive"))
      (node (ref "IC13") (pin "6") (pinfunction "VDDANA_6") (pintype "power_in"))
    )
    (net (code "61") (name "Net-(IC13B-VDDCORE)") (class "Default")
      (node (ref "C49") (pin "2") (pinfunction "2_2") (pintype "passive"))
      (node (ref "IC13") (pin "43") (pinfunction "VDDCORE_43") (pintype "power_in"))
    )
    (net (code "62") (name "Net-(IC14-~{HOLD}{slash}IO3)") (class "Default")
      (node (ref "IC14") (pin "3") (pinfunction "~{WP}/IO2_3") (pintype "bidirectional"))
      (node (ref "IC14") (pin "7") (pinfunction "~{HOLD}/IO3_7") (pintype "bidirectional"))
      (node (ref "R70") (pin "1") (pinfunction "1_1") (pintype "passive"))
    )
    (net (code "63") (name "Net-(IC15-RO)") (class "Default")
      (node (ref "IC15") (pin "1") (pinfunction "RO_1") (pintype "output"))
      (node (ref "R64") (pin "2") (pinfunction "2_2") (pintype "passive"))
    )
    (net (code "64") (name "Net-(IC17-FB)") (class "Default")
      (node (ref "C57") (pin "1") (pinfunction "1_1") (pintype "passive"))
      (node (ref "IC17") (pin "6") (pinfunction "FB_6") (pintype "input"))
      (node (ref "R74") (pin "1") (pinfunction "1_1") (pintype "passive"))
      (node (ref "R75") (pin "2") (pinfunction "2_2") (pintype "passive"))
    )
    (net (code "65") (name "Net-(IC17-LX)") (class "Default")
      (node (ref "IC17") (pin "4") (pinfunction "LX_4") (pintype "output"))
      (node (ref "L3") (pin "1") (pinfunction "1_1") (pintype "passive"))
    )
    (net (code "66") (name "Net-(JP2-E1)") (class "Default")
      (node (ref "JP2") (pin "1") (pinfunction "E1_1") (pintype "passive"))
      (node (ref "R59") (pin "2") (pinfunction "2_2") (pintype "passive"))
    )
    (net (code "67") (name "Net-(LD3-A)") (class "Default")
      (node (ref "LD3") (pin "2") (pinfunction "A_2") (pintype "passive"))
      (node (ref "R71") (pin "1") (pinfunction "1_1") (pintype "passive"))
    )
    (net (code "68") (name "Net-(LD4-A)") (class "Default")
      (node (ref "LD4") (pin "2") (pinfunction "A_2") (pintype "passive"))
      (node (ref "R72") (pin "1") (pinfunction "1_1") (pintype "passive"))
    )
    (net (code "69") (name "Net-(LD5-A)") (class "Default")
      (node (ref "LD5") (pin "2") (pinfunction "A_2") (pintype "passive"))
      (node (ref "R73") (pin "1") (pinfunction "1_1") (pintype "passive"))
    )
    (net (code "70") (name "Net-(PB1-Pad2)") (class "Default")
      (node (ref "PB1") (pin "2") (pinfunction "2_2") (pintype "bidirectional"))
      (node (ref "R68") (pin "2") (pinfunction "2_2") (pintype "passive"))
    )
    (net (code "71") (name "P3V3") (class "Default")
      (node (ref "C41") (pin "2") (pinfunction "2_2") (pintype "passive"))
      (node (ref "C50") (pin "1") (pinfunction "1_1") (pintype "passive"))
      (node (ref "C52") (pin "1") (pinfunction "1_1") (pintype "passive"))
      (node (ref "C53") (pin "1") (pinfunction "1_1") (pintype "passive"))
      (node (ref "C54") (pin "1") (pinfunction "1_1") (pintype "passive"))
      (node (ref "C56") (pin "1") (pinfunction "1_1") (pintype "passive"))
      (node (ref "C57") (pin "2") (pinfunction "2_2") (pintype "passive"))
      (node (ref "D3") (pin "1") (pinfunction "C_1") (pintype "passive"))
      (node (ref "FB2") (pin "1") (pinfunction "1_1") (pintype "passive"))
      (node (ref "IC11") (pin "20") (pinfunction "VDD_20") (pintype "power_in"))
      (node (ref "IC12") (pin "4") (pinfunction "VCC_4") (pintype "power_in"))
      (node (ref "IC13") (pin "17") (pinfunction "VDDIO_17") (pintype "power_in"))
      (node (ref "IC13") (pin "36") (pinfunction "VDDIO_36") (pintype "power_in"))
      (node (ref "IC13") (pin "44") (pinfunction "VDDIN_44") (pintype "power_in"))
      (node (ref "IC14") (pin "8") (pinfunction "VCC_8") (pintype "power_in"))
      (node (ref "IC7") (pin "1") (pinfunction "E0_1") (pintype "input"))
      (node (ref "IC7") (pin "8") (pinfunction "VCC_8") (pintype "power_in"))
      (node (ref "JP3") (pin "1") (pinfunction "1_1") (pintype "passive"))
      (node (ref "L3") (pin "2") (pinfunction "2_2") (pintype "passive"))
      (node (ref "R56") (pin "1") (pinfunction "1_1") (pintype "passive"))
      (node (ref "R62") (pin "2") (pinfunction "2_2") (pintype "passive"))
      (node (ref "R63") (pin "2") (pinfunction "2_2") (pintype "passive"))
      (node (ref "R66") (pin "1") (pinfunction "1_1") (pintype "passive"))
      (node (ref "R67") (pin "2") (pinfunction "2_2") (pintype "passive"))
      (node (ref "R69") (pin "2") (pinfunction "2_2") (pintype "passive"))
      (node (ref "R70") (pin "2") (pinfunction "2_2") (pintype "passive"))
      (node (ref "R71") (pin "2") (pinfunction "2_2") (pintype "passive"))
      (node (ref "R72") (pin "2") (pinfunction "2_2") (pintype "passive"))
      (node (ref "R73") (pin "2") (pinfunction "2_2") (pintype "passive"))
      (node (ref "R74") (pin "2") (pinfunction "2_2") (pintype "passive"))
    )
    (net (code "72") (name "P5V0") (class "Default")
      (node (ref "C42") (pin "2") (pinfunction "2_2") (pintype "passive"))
      (node (ref "C47") (pin "1") (pinfunction "1_1") (pintype "passive"))
      (node (ref "C55") (pin "2") (pinfunction "2_2") (pintype "passive"))
      (node (ref "D12") (pin "4") (pinfunction "VCC_4") (pintype "power_in"))
      (node (ref "IC10") (pin "3") (pinfunction "VDD_3") (pintype "power_in"))
      (node (ref "IC15") (pin "8") (pinfunction "VCC_8") (pintype "power_in"))
      (node (ref "IC17") (pin "2") (pinfunction "EN_2") (pintype "input"))
      (node (ref "IC17") (pin "3") (pinfunction "VIN_3") (pintype "input"))
      (node (ref "J1") (pin "1") (pinfunction "VBUS_1") (pintype "power_in"))
    )
    (net (code "73") (name "P12V0") (class "Default")
      (node (ref "J4") (pin "1") (pinfunction "1_1") (pintype "bidirectional"))
      (node (ref "J5") (pin "1") (pinfunction "1_1") (pintype "bidirectional"))
    )
    (net (code "74") (name "unconnected-(IC10-VREF-Pad5)") (class "Default")
      (node (ref "IC10") (pin "5") (pinfunction "VREF_5") (pintype "output"))
    )
    (net (code "75") (name "unconnected-(IC11-CLKOUT{slash}SOF-Pad3)") (class "Default")
      (node (ref "IC11") (pin "3") (pinfunction "CLKOUT/SOF_3") (pintype "output"))
    )
    (net (code "76") (name "unconnected-(IC11-RX0BF#-Pad12)") (class "Default")
      (node (ref "IC11") (pin "12") (pinfunction "RX0BF#_12") (pintype "output"))
    )
    (net (code "77") (name "unconnected-(IC11-RX1BF#-Pad11)") (class "Default")
      (node (ref "IC11") (pin "11") (pinfunction "RX1BF#_11") (pintype "output"))
    )
    (net (code "78") (name "unconnected-(IC11-TX0RTS#-Pad4)") (class "Default")
      (node (ref "IC11") (pin "4") (pinfunction "TX0RTS#_4") (pintype "input"))
    )
    (net (code "79") (name "unconnected-(IC11-TX1RTS#-Pad5)") (class "Default")
      (node (ref "IC11") (pin "5") (pinfunction "TX1RTS#_5") (pintype "input"))
    )
    (net (code "80") (name "unconnected-(IC11-TX2RTS#-Pad7)") (class "Default")
      (node (ref "IC11") (pin "7") (pinfunction "TX2RTS#_7") (pintype "input"))
    )
    (net (code "81") (name "unconnected-(IC11-nc-Pad6)") (class "Default")
      (node (ref "IC11") (pin "6") (pinfunction "nc_6") (pintype "passive"))
    )
    (net (code "82") (name "unconnected-(IC11-nc-Pad15)") (class "Default")
      (node (ref "IC11") (pin "15") (pinfunction "nc_15") (pintype "passive"))
    )
    (net (code "83") (name "unconnected-(IC17-NC-Pad1)") (class "Default")
      (node (ref "IC17") (pin "1") (pinfunction "NC_1") (pintype "passive"))
    )
    (net (code "84") (name "unconnected-(J1-ID-Pad4)") (class "Default")
      (node (ref "J1") (pin "4") (pinfunction "ID_4") (pintype "passive"))
    )
    (net (code "85") (name "unconnected-(JP3-Pad6)") (class "Default")
      (node (ref "JP3") (pin "6") (pinfunction "6_6") (pintype "passive"))
    )
    (net (code "86") (name "unconnected-(JP3-Pad7)") (class "Default")
      (node (ref "JP3") (pin "7") (pinfunction "7_7") (pintype "passive"))
    )
    (net (code "87") (name "unconnected-(JP3-Pad8)") (class "Default")
      (node (ref "JP3") (pin "8") (pinfunction "8_8") (pintype "passive"))
    )
    (net (code "88") (name "unconnected-(R54-Pad1)") (class "Default")
      (node (ref "R54") (pin "1") (pinfunction "1_1") (pintype "passive"))
    )
  )
)
